# Schematic.net
KiCad netlist of a schematic drawn in Altium Designer
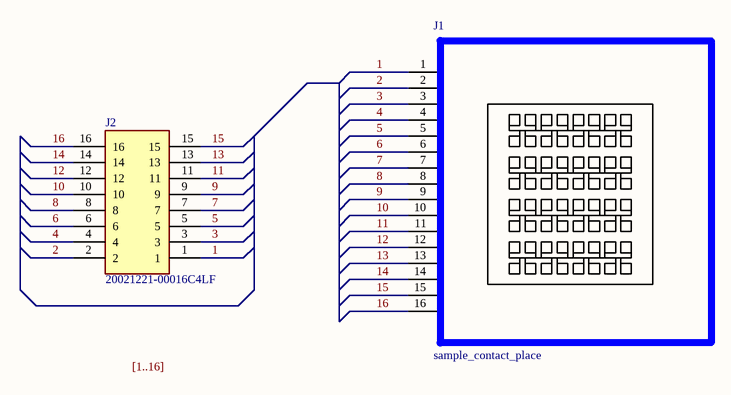
[diagram p0: Schematic.SchDoc]

(export (version "E")
  (design (tool "Eeschema 10.0.6"))
  (components
    (comp (ref "J1")
      (value "sample_contact_place")
      (footprint "sample")
      (libsource (lib "sample_holder_library") (part "sample_contact_place"))
    )
    (comp (ref "J2")
      (value "20021221-00016C4LF")
      (footprint "2002122100016C4LF")
      (description "Connector")
      (libsource (lib "sample_holder_library") (part "20021221-00016C4LF"))
    )
  )
  (nets
    (net (code "1") (name "/1") (class "Default")
      (node (ref "J1") (pin "1") (pinfunction "1_1") (pintype "passive"))
      (node (ref "J2") (pin "1") (pinfunction "1_1") (pintype "passive"))
    )
    (net (code "2") (name "/2") (class "Default")
      (node (ref "J1") (pin "2") (pinfunction "2_2") (pintype "passive"))
      (node (ref "J2") (pin "2") (pinfunction "2_2") (pintype "passive"))
    )
    (net (code "3") (name "/3") (class "Default")
      (node (ref "J1") (pin "3") (pinfunction "3_3") (pintype "passive"))
      (node (ref "J2") (pin "3") (pinfunction "3_3") (pintype "passive"))
    )
    (net (code "4") (name "/4") (class "Default")
      (node (ref "J1") (pin "4") (pinfunction "4_4") (pintype "passive"))
      (node (ref "J2") (pin "4") (pinfunction "4_4") (pintype "passive"))
    )
    (net (code "5") (name "/5") (class "Default")
      (node (ref "J1") (pin "5") (pinfunction "5_5") (pintype "passive"))
      (node (ref "J2") (pin "5") (pinfunction "5_5") (pintype "passive"))
    )
    (net (code "6") (name "/6") (class "Default")
      (node (ref "J1") (pin "6") (pinfunction "6_6") (pintype "passive"))
      (node (ref "J2") (pin "6") (pinfunction "6_6") (pintype "passive"))
    )
    (net (code "7") (name "/7") (class "Default")
      (node (ref "J1") (pin "7") (pinfunction "7_7") (pintype "passive"))
      (node (ref "J2") (pin "7") (pinfunction "7_7") (pintype "passive"))
    )
    (net (code "8") (name "/8") (class "Default")
      (node (ref "J1") (pin "8") (pinfunction "8_8") (pintype "passive"))
      (node (ref "J2") (pin "8") (pinfunction "8_8") (pintype "passive"))
    )
    (net (code "9") (name "/9") (class "Default")
      (node (ref "J1") (pin "9") (pinfunction "9_9") (pintype "passive"))
      (node (ref "J2") (pin "9") (pinfunction "9_9") (pintype "passive"))
    )
    (net (code "10") (name "/10") (class "Default")
      (node (ref "J1") (pin "10") (pinfunction "10_10") (pintype "passive"))
      (node (ref "J2") (pin "10") (pinfunction "10_10") (pintype "passive"))
    )
    (net (code "11") (name "/11") (class "Default")
      (node (ref "J1") (pin "11") (pinfunction "11_11") (pintype "passive"))
      (node (ref "J2") (pin "11") (pinfunction "11_11") (pintype "passive"))
    )
    (net (code "12") (name "/12") (class "Default")
      (node (ref "J1") (pin "12") (pinfunction "12_12") (pintype "passive"))
      (node (ref "J2") (pin "12") (pinfunction "12_12") (pintype "passive"))
    )
    (net (code "13") (name "/13") (class "Default")
      (node (ref "J1") (pin "13") (pinfunction "13_13") (pintype "passive"))
      (node (ref "J2") (pin "13") (pinfunction "13_13") (pintype "passive"))
    )
    (net (code "14") (name "/14") (class "Default")
      (node (ref "J1") (pin "14") (pinfunction "14_14") (pintype "passive"))
      (node (ref "J2") (pin "14") (pinfunction "14_14") (pintype "passive"))
    )
    (net (code "15") (name "/15") (class "Default")
      (node (ref "J1") (pin "15") (pinfunction "15_15") (pintype "passive"))
      (node (ref "J2") (pin "15") (pinfunction "15_15") (pintype "passive"))
    )
    (net (code "16") (name "/16") (class "Default")
      (node (ref "J1") (pin "16") (pinfunction "16_16") (pintype "passive"))
      (node (ref "J2") (pin "16") (pinfunction "16_16") (pintype "passive"))
    )
  )
)
